# automotive-mirror-communication-pin-mark.net
KiCad netlist of a schematic drawn in Altium Designer
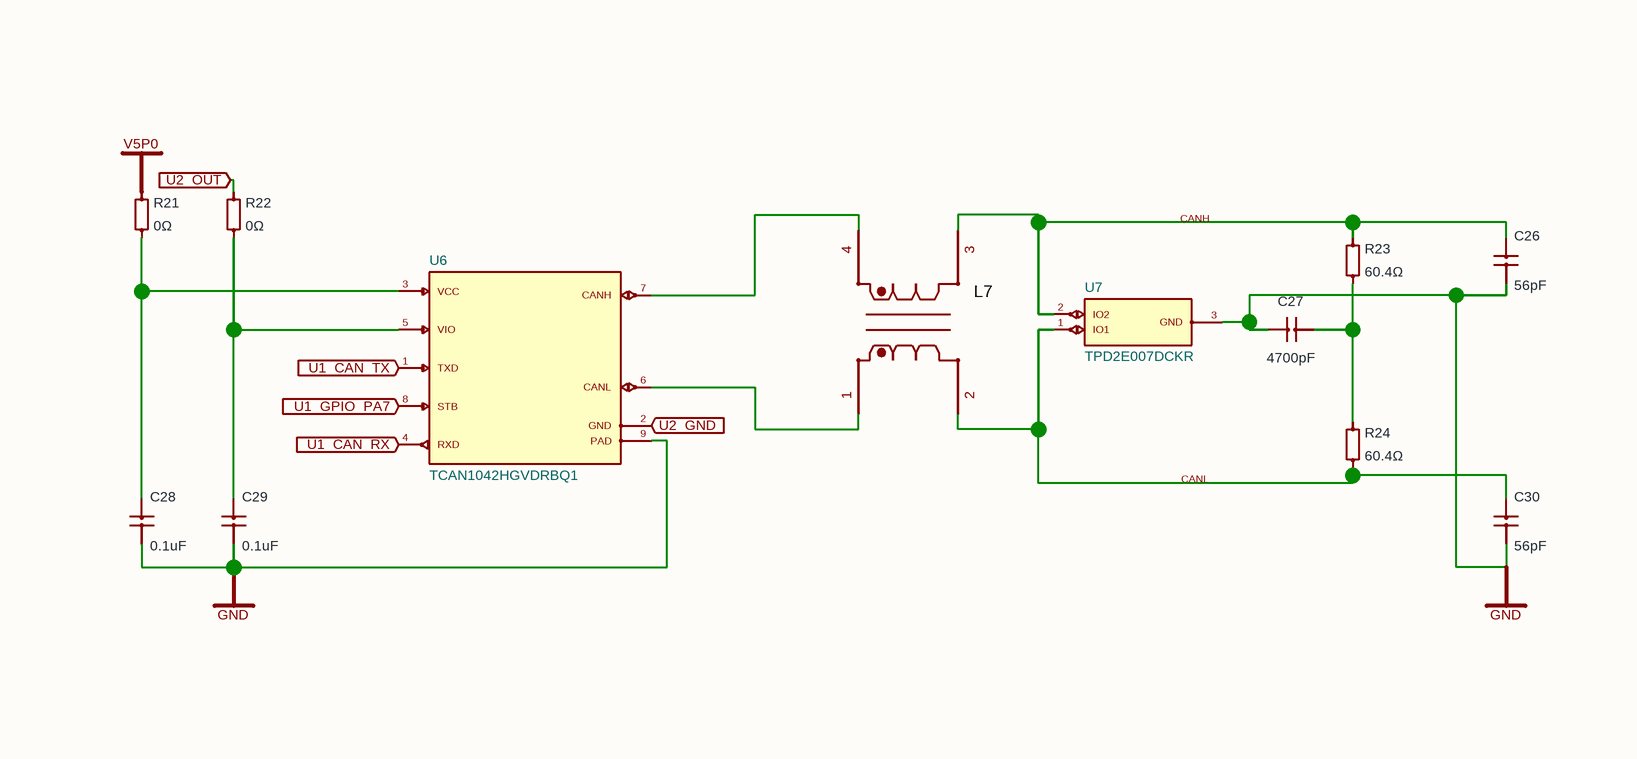
[diagram p0: automotive-mirror-communication-pin-markers.SchDoc]

(export (version "E")
  (design (tool "Eeschema 10.0.6"))
  (components
    (comp (ref "C26") (value "56pF") (libsource (lib "altium-import") (part "root_0_capacitor_down_")))
    (comp (ref "C27") (value "4700pF") (libsource (lib "altium-import") (part "root_0_capacitor_right_")))
    (comp (ref "C28") (value "0.1uF") (libsource (lib "altium-import") (part "root_0_capacitor_down_")))
    (comp (ref "C29") (value "0.1uF") (libsource (lib "altium-import") (part "root_0_capacitor_down_")))
    (comp (ref "C30") (value "56pF") (libsource (lib "altium-import") (part "root_0_capacitor_down_")))
    (comp (ref "L7") (value "~") (libsource (lib "altium-import") (part "root_0_L7_")))
    (comp (ref "R21") (value "0Ω") (libsource (lib "altium-import") (part "root_0_boxresistor_down_")))
    (comp (ref "R22") (value "0Ω") (libsource (lib "altium-import") (part "root_0_boxresistor_down_")))
    (comp (ref "R23") (value "60.4Ω") (libsource (lib "altium-import") (part "root_0_boxresistor_down_")))
    (comp (ref "R24") (value "60.4Ω") (libsource (lib "altium-import") (part "root_0_boxresistor_down_")))
    (comp (ref "U6") (value "~") (libsource (lib "altium-import") (part "root_0_U6_")))
    (comp (ref "U7") (value "~") (libsource (lib "altium-import") (part "root_0_U7_")))
  )
  (nets
    (net (code "1") (name "/U1_CAN_RX") (class "Default")
      (node (ref "U6") (pin "4") (pinfunction "RXD_4") (pintype "passive"))
    )
    (net (code "2") (name "/U1_CAN_TX") (class "Default")
      (node (ref "U6") (pin "1") (pinfunction "TXD_1") (pintype "passive"))
    )
    (net (code "3") (name "/U1_GPIO_PA7") (class "Default")
      (node (ref "U6") (pin "8") (pinfunction "STB_8") (pintype "passive"))
    )
    (net (code "4") (name "/U2_GND") (class "Default")
      (node (ref "U6") (pin "2") (pinfunction "GND_2") (pintype "passive"))
    )
    (net (code "5") (name "/U2_OUT") (class "Default")
      (node (ref "R22") (pin "1") (pinfunction "anode_1") (pintype "passive"))
    )
    (net (code "6") (name "GND") (class "Default")
      (node (ref "C26") (pin "2") (pinfunction "cathode_2") (pintype "passive"))
      (node (ref "C27") (pin "1") (pinfunction "pos_1") (pintype "passive"))
      (node (ref "C28") (pin "2") (pinfunction "cathode_2") (pintype "passive"))
      (node (ref "C29") (pin "2") (pinfunction "cathode_2") (pintype "passive"))
      (node (ref "C30") (pin "2") (pinfunction "cathode_2") (pintype "passive"))
      (node (ref "U6") (pin "9") (pinfunction "PAD_9") (pintype "passive"))
      (node (ref "U7") (pin "3") (pinfunction "GND_3") (pintype "passive"))
    )
    (net (code "7") (name "Net-(C26-anode)") (class "Default")
      (node (ref "C26") (pin "1") (pinfunction "anode_1") (pintype "passive"))
      (node (ref "L7") (pin "3") (pinfunction "pin3_3") (pintype "passive"))
      (node (ref "R23") (pin "1") (pinfunction "anode_1") (pintype "passive"))
      (node (ref "U7") (pin "2") (pinfunction "IO2_2") (pintype "passive"))
    )
    (net (code "8") (name "Net-(C27-neg)") (class "Default")
      (node (ref "C27") (pin "2") (pinfunction "neg_2") (pintype "passive"))
      (node (ref "R23") (pin "2") (pinfunction "cathode_2") (pintype "passive"))
      (node (ref "R24") (pin "1") (pinfunction "anode_1") (pintype "passive"))
    )
    (net (code "9") (name "Net-(C28-anode)") (class "Default")
      (node (ref "C28") (pin "1") (pinfunction "anode_1") (pintype "passive"))
      (node (ref "R21") (pin "2") (pinfunction "cathode_2") (pintype "passive"))
      (node (ref "U6") (pin "3") (pinfunction "VCC_3") (pintype "passive"))
    )
    (net (code "10") (name "Net-(C29-anode)") (class "Default")
      (node (ref "C29") (pin "1") (pinfunction "anode_1") (pintype "passive"))
      (node (ref "R22") (pin "2") (pinfunction "cathode_2") (pintype "passive"))
      (node (ref "U6") (pin "5") (pinfunction "VIO_5") (pintype "passive"))
    )
    (net (code "11") (name "Net-(C30-anode)") (class "Default")
      (node (ref "C30") (pin "1") (pinfunction "anode_1") (pintype "passive"))
      (node (ref "L7") (pin "2") (pinfunction "pin2_2") (pintype "passive"))
      (node (ref "R24") (pin "2") (pinfunction "cathode_2") (pintype "passive"))
      (node (ref "U7") (pin "1") (pinfunction "IO1_1") (pintype "passive"))
    )
    (net (code "12") (name "Net-(L7-pin1)") (class "Default")
      (node (ref "L7") (pin "1") (pinfunction "pin1_1") (pintype "passive"))
      (node (ref "U6") (pin "6") (pinfunction "CANL_6") (pintype "passive"))
    )
    (net (code "13") (name "Net-(L7-pin4)") (class "Default")
      (node (ref "L7") (pin "4") (pinfunction "pin4_4") (pintype "passive"))
      (node (ref "U6") (pin "7") (pinfunction "CANH_7") (pintype "passive"))
    )
    (net (code "14") (name "V5P0") (class "Default")
      (node (ref "R21") (pin "1") (pinfunction "anode_1") (pintype "passive"))
    )
  )
)
